# USB_Connectors.net
KiCad netlist of a schematic drawn in Altium Designer
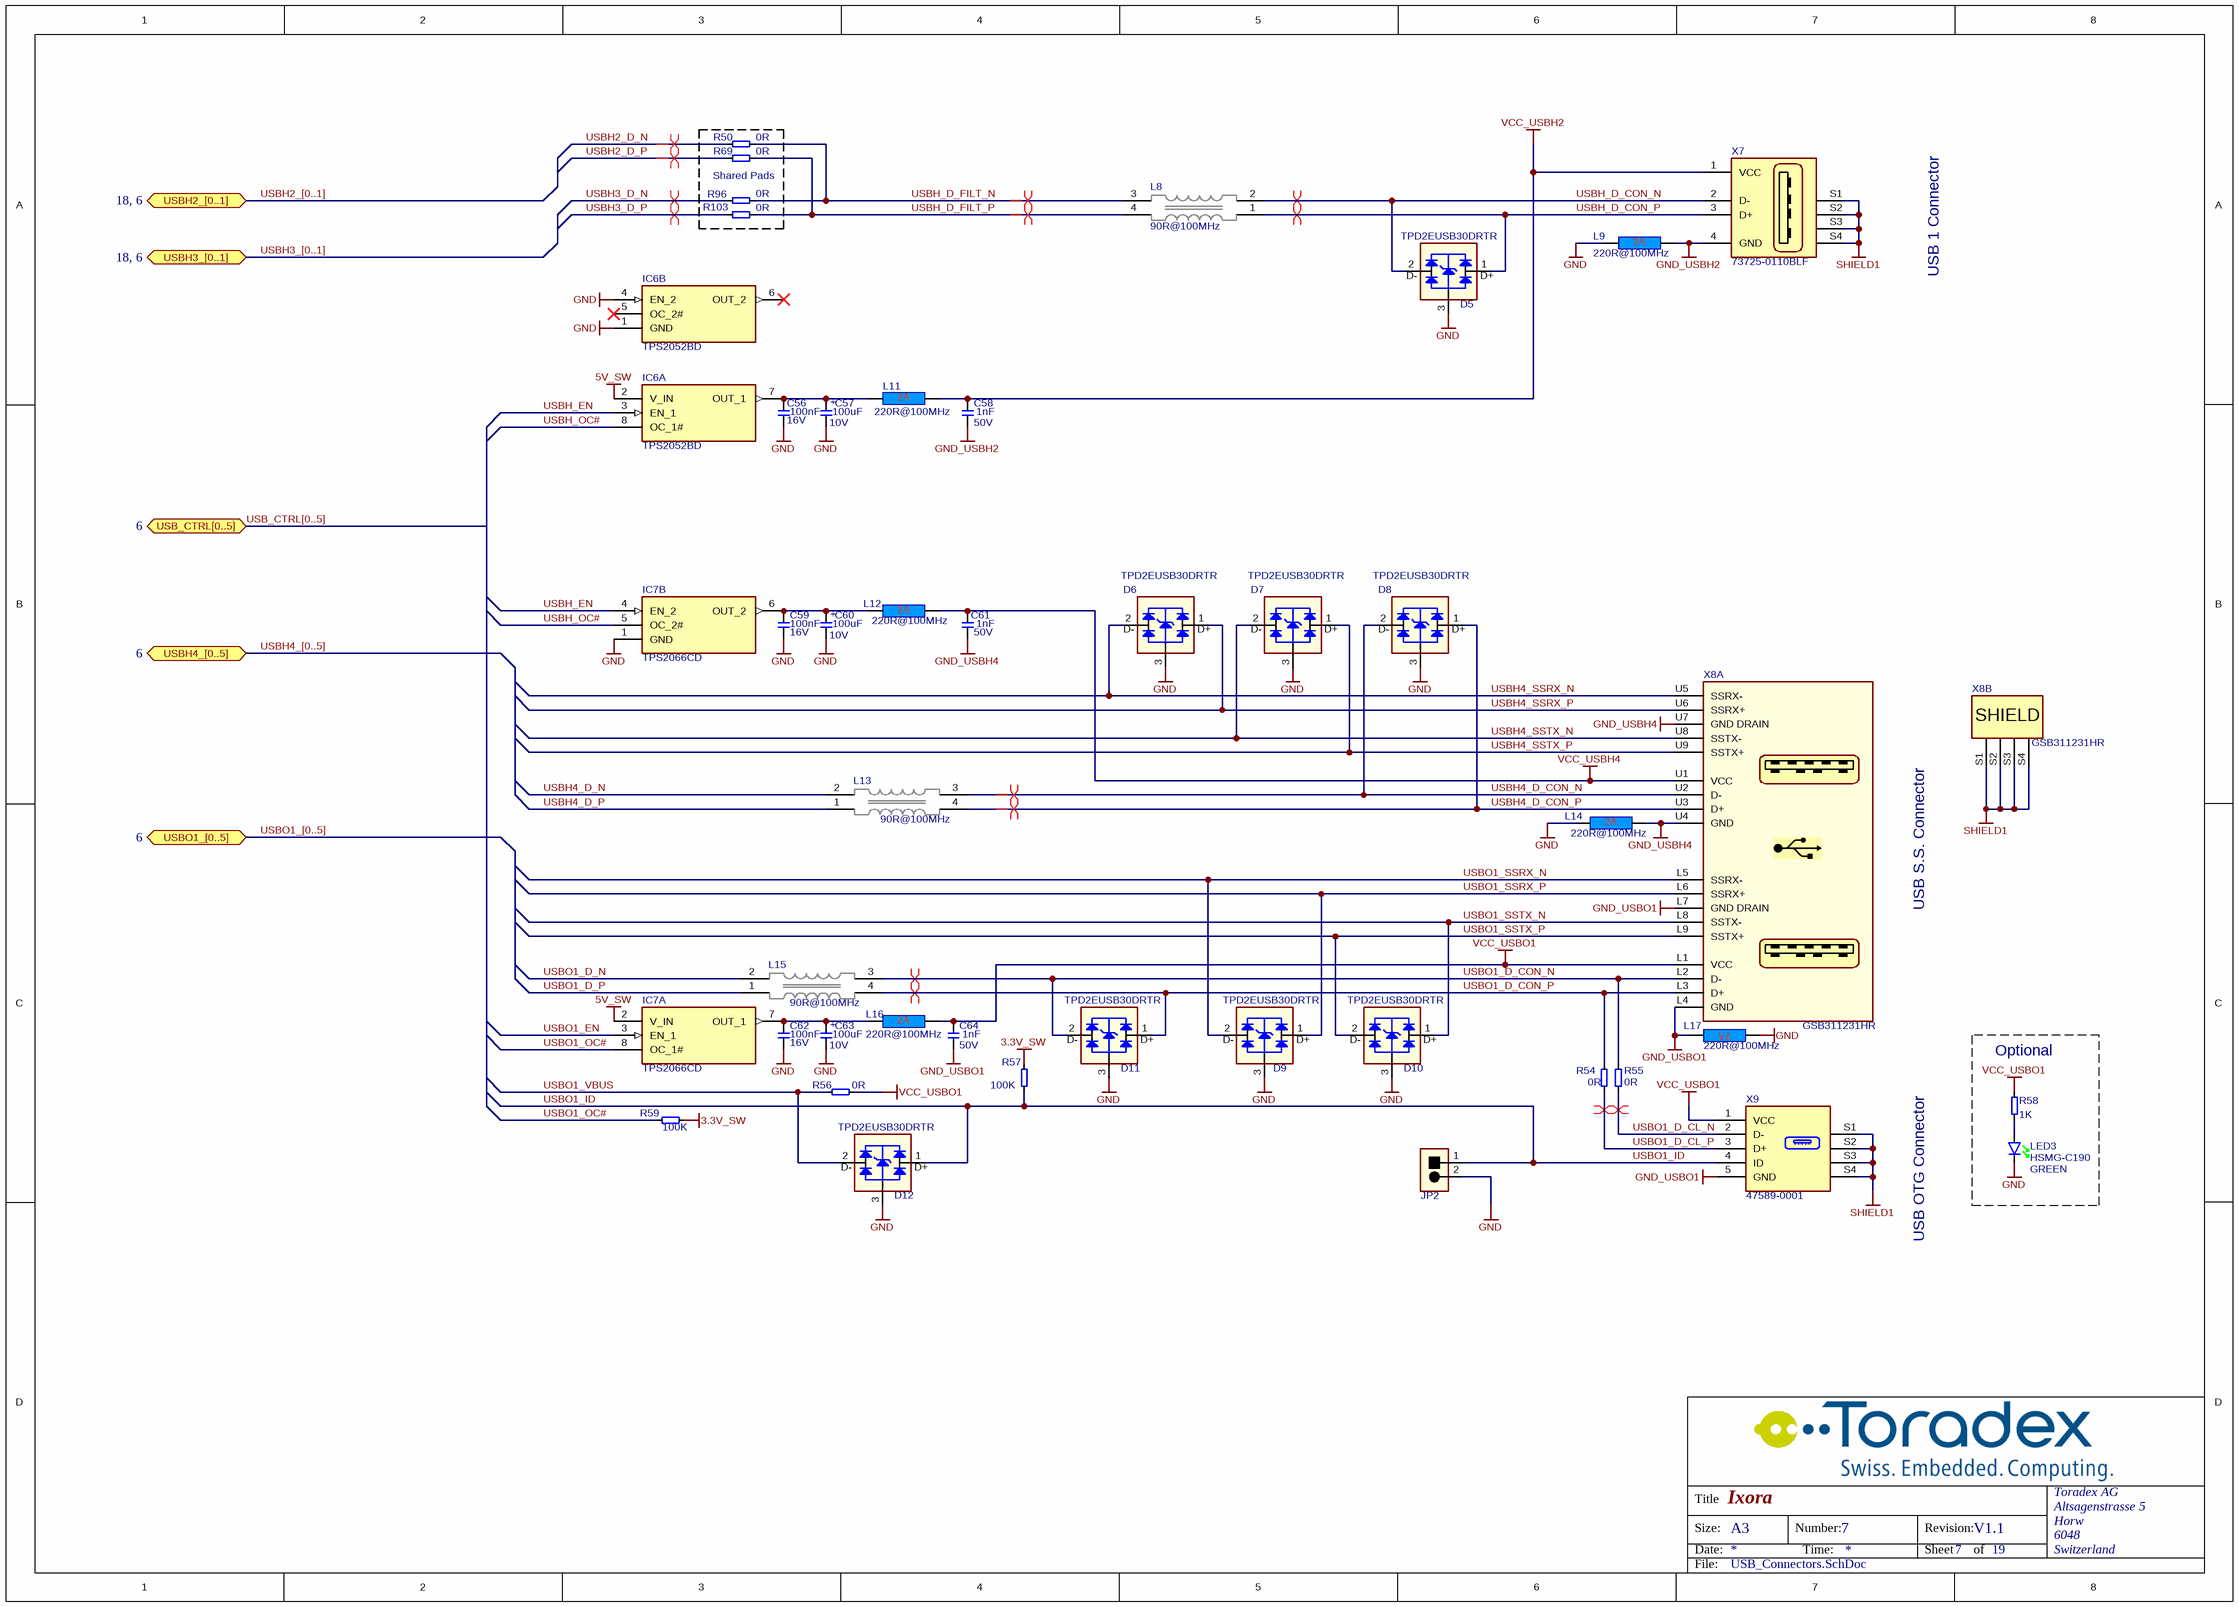
[diagram p0: USB_Connectors.SchDoc]

(export (version "E")
  (design (tool "Eeschema 10.0.6"))
  (components
    (comp (ref "C56")
      (value "100nF")
      (footprint "CAPC1005X60N")
      (description "Capacitor Ceramic X7R 100nF 16V 10% 0402")
      (fields (field (name "TOLERANCE") "10%") (field (name "RATING") "16V"))
      (libsource (lib "Ixora") (part "C-X7R-100nF-16V-10%-0402"))
    )
    (comp (ref "C57")
      (value "100uF")
      (footprint "CAPMP6032X280N")
      (description "Capacitor TA 100uF 10V 10% 6032")
      (fields (field (name "TOLERANCE") "10%") (field (name "RATING") "10V"))
      (libsource (lib "Ixora") (part "C-TA-100uF-10V-10%-6032"))
    )
    (comp (ref "C58")
      (value "1nF")
      (footprint "CAPC1005X60N")
      (description "Capacitor Ceramic X7R 1nF 50V 10% 0402")
      (fields (field (name "TOLERANCE") "10%") (field (name "RATING") "50V"))
      (libsource (lib "Ixora") (part "C-X7R-1nF-50V-10%-0402"))
    )
    (comp (ref "C59")
      (value "100nF")
      (footprint "CAPC1005X60N")
      (description "Capacitor Ceramic X7R 100nF 16V 10% 0402")
      (fields (field (name "TOLERANCE") "10%") (field (name "RATING") "16V"))
      (libsource (lib "Ixora") (part "C-X7R-100nF-16V-10%-0402"))
    )
    (comp (ref "C60")
      (value "100uF")
      (footprint "CAPMP6032X280N")
      (description "Capacitor TA 100uF 10V 10% 6032")
      (fields (field (name "TOLERANCE") "10%") (field (name "RATING") "10V"))
      (libsource (lib "Ixora") (part "C-TA-100uF-10V-10%-6032"))
    )
    (comp (ref "C61")
      (value "1nF")
      (footprint "CAPC1005X60N")
      (description "Capacitor Ceramic X7R 1nF 50V 10% 0402")
      (fields (field (name "TOLERANCE") "10%") (field (name "RATING") "50V"))
      (libsource (lib "Ixora") (part "C-X7R-1nF-50V-10%-0402"))
    )
    (comp (ref "C62")
      (value "100nF")
      (footprint "CAPC1005X60N")
      (description "Capacitor Ceramic X7R 100nF 16V 10% 0402")
      (fields (field (name "TOLERANCE") "10%") (field (name "RATING") "16V"))
      (libsource (lib "Ixora") (part "C-X7R-100nF-16V-10%-0402"))
    )
    (comp (ref "C63")
      (value "100uF")
      (footprint "CAPMP6032X280N")
      (description "Capacitor TA 100uF 10V 10% 6032")
      (fields (field (name "TOLERANCE") "10%") (field (name "RATING") "10V"))
      (libsource (lib "Ixora") (part "C-TA-100uF-10V-10%-6032"))
    )
    (comp (ref "C64")
      (value "1nF")
      (footprint "CAPC1005X60N")
      (description "Capacitor Ceramic X7R 1nF 50V 10% 0402")
      (fields (field (name "TOLERANCE") "10%") (field (name "RATING") "50V"))
      (libsource (lib "Ixora") (part "C-X7R-1nF-50V-10%-0402"))
    )
    (comp (ref "D5")
      (value "TPD2EUSB30DRTR")
      (footprint "T_TI_TPD2EUSB30DRTR")
      (description "2 Channel Protection for Super Speed USB3.0")
      (fields (field (name "MANUFACTURER PART NO.") "TPD2EUSB30DRTR"))
      (libsource (lib "Ixora") (part "D-TI-TPD2EUSB30DRTR"))
    )
    (comp (ref "D6")
      (value "TPD2EUSB30DRTR")
      (footprint "T_TI_TPD2EUSB30DRTR")
      (description "2 Channel Protection for Super Speed USB3.0")
      (fields (field (name "MANUFACTURER PART NO.") "TPD2EUSB30DRTR"))
      (libsource (lib "Ixora") (part "D-TI-TPD2EUSB30DRTR"))
    )
    (comp (ref "D7")
      (value "TPD2EUSB30DRTR")
      (footprint "T_TI_TPD2EUSB30DRTR")
      (description "2 Channel Protection for Super Speed USB3.0")
      (fields (field (name "MANUFACTURER PART NO.") "TPD2EUSB30DRTR"))
      (libsource (lib "Ixora") (part "D-TI-TPD2EUSB30DRTR"))
    )
    (comp (ref "D8")
      (value "TPD2EUSB30DRTR")
      (footprint "T_TI_TPD2EUSB30DRTR")
      (description "2 Channel Protection for Super Speed USB3.0")
      (fields (field (name "MANUFACTURER PART NO.") "TPD2EUSB30DRTR"))
      (libsource (lib "") (part "D-TI-TPD2EUSB30DRTR_2"))
    )
    (comp (ref "D9")
      (value "TPD2EUSB30DRTR")
      (footprint "T_TI_TPD2EUSB30DRTR")
      (description "2 Channel Protection for Super Speed USB3.0")
      (fields (field (name "MANUFACTURER PART NO.") "TPD2EUSB30DRTR"))
      (libsource (lib "Ixora") (part "D-TI-TPD2EUSB30DRTR"))
    )
    (comp (ref "D10")
      (value "TPD2EUSB30DRTR")
      (footprint "T_TI_TPD2EUSB30DRTR")
      (description "2 Channel Protection for Super Speed USB3.0")
      (fields (field (name "MANUFACTURER PART NO.") "TPD2EUSB30DRTR"))
      (libsource (lib "") (part "D-TI-TPD2EUSB30DRTR_1"))
    )
    (comp (ref "D11")
      (value "TPD2EUSB30DRTR")
      (footprint "T_TI_TPD2EUSB30DRTR")
      (description "2 Channel Protection for Super Speed USB3.0")
      (fields (field (name "MANUFACTURER PART NO.") "TPD2EUSB30DRTR"))
      (libsource (lib "Ixora") (part "D-TI-TPD2EUSB30DRTR"))
    )
    (comp (ref "D12")
      (value "TPD2EUSB30DRTR")
      (footprint "T_TI_TPD2EUSB30DRTR")
      (description "2 Channel Protection for Super Speed USB3.0")
      (fields (field (name "MANUFACTURER PART NO.") "TPD2EUSB30DRTR"))
      (libsource (lib "Ixora") (part "D-TI-TPD2EUSB30DRTR"))
    )
    (comp (ref "IC6")
      (value "TPS2052BD")
      (footprint "SOIC127P600X173-8N")
      (description "Dual High Side Switch With OC_DET 500mA/CH")
      (fields (field (name "MANUFACTURER PART NO.") "TPS2052BD"))
      (libsource (lib "Ixora") (part "IC-TI-TPS2052BD"))
    )
    (comp (ref "IC7")
      (value "TPS2066CD")
      (footprint "SOIC127P600X173-8N")
      (description "1A Dual High Side Switch (Current Limiting (Fixed), Over Temperature, Reverse Current, UVLO)")
      (fields (field (name "MANUFACTURER PART NO.") "TPS2066CD"))
      (libsource (lib "Ixora") (part "IC-TI-TPS2066CD"))
    )
    (comp (ref "JP2")
      (value "TSW-101-07-G-D")
      (footprint "T_Samtec_TSW-101-07-G-D")
      (description "Header male, 1x2 Pins, 2.54 mm pitch")
      (libsource (lib "Ixora") (part "CON-Samtec-TSW-101-07-G-D"))
    )
    (comp (ref "L8")
      (value "90R@100MHz")
      (footprint "T_Murata_DLW21SN900SQ2")
      (description "Common Mode Choke High Speed 90R 330mA")
      (fields (field (name "TOLERANCE") "25%") (field (name "MANUFACTURER PART NO.") "DLW21SN900SQ2"))
      (libsource (lib "") (part "L-Murata-DLW21SN900SQ2-90R@100MHz-330mA-25%_1"))
    )
    (comp (ref "L9")
      (value "220R@100MHz")
      (footprint "INDC1608X95N")
      (description "220R@100MHz 2A EMI FILTER")
      (fields (field (name "TOLERANCE") "25%"))
      (libsource (lib "Ixora") (part "L-220R@100MHz-2A-25%-0603"))
    )
    (comp (ref "L11")
      (value "220R@100MHz")
      (footprint "INDC1608X95N")
      (description "220R@100MHz 2A EMI FILTER")
      (fields (field (name "TOLERANCE") "25%"))
      (libsource (lib "Ixora") (part "L-220R@100MHz-2A-25%-0603"))
    )
    (comp (ref "L12")
      (value "220R@100MHz")
      (footprint "INDC1608X95N")
      (description "220R@100MHz 2A EMI FILTER")
      (fields (field (name "TOLERANCE") "25%"))
      (libsource (lib "Ixora") (part "L-220R@100MHz-2A-25%-0603"))
    )
    (comp (ref "L13")
      (value "90R@100MHz")
      (footprint "T_Murata_DLW21SN900SQ2")
      (description "Common Mode Choke High Speed 90R 330mA")
      (fields (field (name "TOLERANCE") "25%") (field (name "MANUFACTURER PART NO.") "DLW21SN900SQ2"))
      (libsource (lib "Ixora") (part "L-Murata-DLW21SN900SQ2-90R@100MHz-330mA-25%"))
    )
    (comp (ref "L14")
      (value "220R@100MHz")
      (footprint "INDC1608X95N")
      (description "220R@100MHz 2A EMI FILTER")
      (fields (field (name "TOLERANCE") "25%"))
      (libsource (lib "Ixora") (part "L-220R@100MHz-2A-25%-0603"))
    )
    (comp (ref "L15")
      (value "90R@100MHz")
      (footprint "T_Murata_DLW21SN900SQ2")
      (description "Common Mode Choke High Speed 90R 330mA")
      (fields (field (name "TOLERANCE") "25%") (field (name "MANUFACTURER PART NO.") "DLW21SN900SQ2"))
      (libsource (lib "Ixora") (part "L-Murata-DLW21SN900SQ2-90R@100MHz-330mA-25%"))
    )
    (comp (ref "L16")
      (value "220R@100MHz")
      (footprint "INDC1608X95N")
      (description "220R@100MHz 2A EMI FILTER")
      (fields (field (name "TOLERANCE") "25%"))
      (libsource (lib "Ixora") (part "L-220R@100MHz-2A-25%-0603"))
    )
    (comp (ref "L17")
      (value "220R@100MHz")
      (footprint "INDC1608X95N")
      (description "220R@100MHz 2A EMI FILTER")
      (fields (field (name "TOLERANCE") "25%"))
      (libsource (lib "") (part "L-220R@100MHz-2A-25%-0603_1"))
    )
    (comp (ref "LED3")
      (value "LED")
      (footprint "LEDC1608X80N_G")
      (description "Surface mount LED green 20mA")
      (fields (field (name "MANUFACTURER PART NO.") "HSMG-C190") (field (name "COLOR") "GREEN"))
      (libsource (lib "Ixora") (part "LED-Avago-HSMG-C190"))
    )
    (comp (ref "R50")
      (value "0R")
      (footprint "T_RESC0603X30N")
      (description "Resistor 0 ohm 63mW 1% 0603")
      (fields (field (name "TOLERANCE") "1%"))
      (libsource (lib "Ixora") (part "R-0R-63mW-1%-0603"))
    )
    (comp (ref "R54")
      (value "0R")
      (footprint "RESC1005X40N")
      (description "Resistor 0 ohm 63mW 1% 0402")
      (fields (field (name "TOLERANCE") "1%"))
      (libsource (lib "Ixora") (part "R-0R-63mW-1%-0402"))
    )
    (comp (ref "R55")
      (value "0R")
      (footprint "RESC1005X40N")
      (description "Resistor 0 ohm 63mW 1% 0402")
      (fields (field (name "TOLERANCE") "1%"))
      (libsource (lib "Ixora") (part "R-0R-63mW-1%-0402"))
    )
    (comp (ref "R56")
      (value "0R")
      (footprint "RESC1005X40N")
      (description "Resistor 0 ohm 63mW 1% 0402")
      (fields (field (name "TOLERANCE") "1%"))
      (libsource (lib "Ixora") (part "R-0R-63mW-1%-0402"))
    )
    (comp (ref "R57")
      (value "100K")
      (footprint "RESC1005X40N")
      (description "Resistor 100 Kohm 63mW 5% 0402")
      (fields (field (name "TOLERANCE") "5%"))
      (libsource (lib "Ixora") (part "R-100KR-63mW-5%-0402"))
    )
    (comp (ref "R58")
      (value "1K")
      (footprint "RESC1005X40N")
      (description "Resistor 1 Kohm 63mW 5% 0402")
      (fields (field (name "TOLERANCE") "5%"))
      (libsource (lib "Ixora") (part "R-1KR-63mW-5%-0402"))
    )
    (comp (ref "R59")
      (value "100K")
      (footprint "RESC1005X40N")
      (description "Resistor 100 Kohm 63mW 5% 0402")
      (fields (field (name "TOLERANCE") "5%"))
      (libsource (lib "Ixora") (part "R-100KR-63mW-5%-0402"))
    )
    (comp (ref "R69")
      (value "0R")
      (footprint "T_RESC0603X30N")
      (description "Resistor 0 ohm 63mW 1% 0603")
      (fields (field (name "TOLERANCE") "1%"))
      (libsource (lib "Ixora") (part "R-0R-63mW-1%-0603"))
    )
    (comp (ref "R96")
      (value "0R")
      (footprint "T_RESC0603X30N")
      (description "Resistor 0 ohm 63mW 1% 0603")
      (fields (field (name "TOLERANCE") "1%"))
      (libsource (lib "Ixora") (part "R-0R-63mW-1%-0603"))
    )
    (comp (ref "R103")
      (value "0R")
      (footprint "T_RESC0603X30N")
      (description "Resistor 0 ohm 63mW 1% 0603")
      (fields (field (name "TOLERANCE") "1%"))
      (libsource (lib "Ixora") (part "R-0R-63mW-1%-0603"))
    )
    (comp (ref "X7")
      (value "CON-Fci-73725-0110BLF")
      (footprint "T_FCI_73725-0110BLF")
      (description "USB Type A Connector")
      (fields (field (name "MANUFACTURER PART NO.") "73725-0110BLF"))
      (libsource (lib "Ixora") (part "CON-Fci-73725-0110BLF"))
    )
    (comp (ref "X8")
      (value "GSB311231HR")
      (footprint "T_AMPHENOL_ GSB311231HR")
      (description "USB 3.0 double row, Type A")
      (fields (field (name "MANUFACTURER PART NO.") "GSB311231HR"))
      (libsource (lib "Ixora") (part "CON-Amphenol-GSB311231HR"))
    )
    (comp (ref "X9")
      (value "CON-Molex-47589-0001-5-0.65")
      (footprint "T_Molex_47589-0001")
      (description "Micro USB OTG Connector")
      (fields (field (name "MANUFACTURER PART NO.") "47589-0001"))
      (libsource (lib "Ixora") (part "CON-Molex-47589-0001-5-0.65"))
    )
  )
  (nets
    (net (code "23") (name "/USBH2_D_N") (class "Default")
      (node (ref "R50") (pin "1") (pinfunction "1_1") (pintype "passive"))
    )
    (net (code "24") (name "/USBH2_D_P") (class "Default")
      (node (ref "R69") (pin "1") (pinfunction "1_1") (pintype "passive"))
    )
    (net (code "26") (name "/USBH3_D_N") (class "Default")
      (node (ref "R96") (pin "1") (pinfunction "1_1") (pintype "passive"))
    )
    (net (code "27") (name "/USBH3_D_P") (class "Default")
      (node (ref "R103") (pin "1") (pinfunction "1_1") (pintype "passive"))
    )
    (net (code "29") (name "/USBH4_D_CON_N") (class "Default")
      (node (ref "D8") (pin "2") (pinfunction "D-_2") (pintype "power_in"))
      (node (ref "L13") (pin "3") (pinfunction "3_3") (pintype "passive"))
      (node (ref "X8") (pin "U2") (pinfunction "D-_U2") (pintype "passive"))
    )
    (net (code "30") (name "/USBH4_D_CON_P") (class "Default")
      (node (ref "D8") (pin "1") (pinfunction "D+_1") (pintype "power_in"))
      (node (ref "L13") (pin "4") (pinfunction "4_4") (pintype "passive"))
      (node (ref "X8") (pin "U3") (pinfunction "D+_U3") (pintype "passive"))
    )
    (net (code "31") (name "/USBH4_D_N") (class "Default")
      (node (ref "L13") (pin "2") (pinfunction "2_2") (pintype "passive"))
    )
    (net (code "32") (name "/USBH4_D_P") (class "Default")
      (node (ref "L13") (pin "1") (pinfunction "1_1") (pintype "passive"))
    )
    (net (code "33") (name "/USBH4_SSRX_N") (class "Default")
      (node (ref "D6") (pin "2") (pinfunction "D-_2") (pintype "power_in"))
      (node (ref "X8") (pin "U5") (pinfunction "SSRX-_U5") (pintype "power_in"))
    )
    (net (code "34") (name "/USBH4_SSRX_P") (class "Default")
      (node (ref "D6") (pin "1") (pinfunction "D+_1") (pintype "power_in"))
      (node (ref "X8") (pin "U6") (pinfunction "SSRX+_U6") (pintype "power_in"))
    )
    (net (code "35") (name "/USBH4_SSTX_N") (class "Default")
      (node (ref "D7") (pin "2") (pinfunction "D-_2") (pintype "power_in"))
      (node (ref "X8") (pin "U8") (pinfunction "SSTX-_U8") (pintype "power_in"))
    )
    (net (code "36") (name "/USBH4_SSTX_P") (class "Default")
      (node (ref "D7") (pin "1") (pinfunction "D+_1") (pintype "power_in"))
      (node (ref "X8") (pin "U9") (pinfunction "SSTX+_U9") (pintype "power_in"))
    )
    (net (code "38") (name "/USBH_D_CON_N") (class "Default")
      (node (ref "D5") (pin "2") (pinfunction "D-_2") (pintype "power_in"))
      (node (ref "L8") (pin "2") (pinfunction "2_2") (pintype "passive"))
      (node (ref "X7") (pin "2") (pinfunction "D-_2") (pintype "passive"))
    )
    (net (code "39") (name "/USBH_D_CON_P") (class "Default")
      (node (ref "D5") (pin "1") (pinfunction "D+_1") (pintype "power_in"))
      (node (ref "L8") (pin "1") (pinfunction "1_1") (pintype "passive"))
      (node (ref "X7") (pin "3") (pinfunction "D+_3") (pintype "passive"))
    )
    (net (code "40") (name "/USBH_D_FILT_N") (class "Default")
      (node (ref "L8") (pin "3") (pinfunction "3_3") (pintype "passive"))
      (node (ref "R50") (pin "2") (pinfunction "2_2") (pintype "passive"))
      (node (ref "R96") (pin "2") (pinfunction "2_2") (pintype "passive"))
    )
    (net (code "41") (name "/USBH_D_FILT_P") (class "Default")
      (node (ref "L8") (pin "4") (pinfunction "4_4") (pintype "passive"))
      (node (ref "R103") (pin "2") (pinfunction "2_2") (pintype "passive"))
      (node (ref "R69") (pin "2") (pinfunction "2_2") (pintype "passive"))
    )
    (net (code "42") (name "/USBH_EN") (class "Default")
      (node (ref "IC6") (pin "3") (pinfunction "EN_1_3") (pintype "input"))
      (node (ref "IC7") (pin "4") (pinfunction "EN_2_4") (pintype "input"))
    )
    (net (code "43") (name "/USBH_OC#") (class "Default")
      (node (ref "IC6") (pin "8") (pinfunction "OC_1#_8") (pintype "passive"))
      (node (ref "IC7") (pin "5") (pinfunction "OC_2#_5") (pintype "passive"))
    )
    (net (code "44") (name "/USBO1_D_CL_N") (class "Default")
      (node (ref "R55") (pin "1") (pinfunction "1_1") (pintype "passive"))
      (node (ref "X9") (pin "2") (pinfunction "D-_2") (pintype "passive"))
    )
    (net (code "45") (name "/USBO1_D_CL_P") (class "Default")
      (node (ref "R54") (pin "1") (pinfunction "1_1") (pintype "passive"))
      (node (ref "X9") (pin "3") (pinfunction "D+_3") (pintype "passive"))
    )
    (net (code "46") (name "/USBO1_D_CON_N") (class "Default")
      (node (ref "D11") (pin "2") (pinfunction "D-_2") (pintype "power_in"))
      (node (ref "L15") (pin "3") (pinfunction "3_3") (pintype "passive"))
      (node (ref "R55") (pin "2") (pinfunction "2_2") (pintype "passive"))
      (node (ref "X8") (pin "L2") (pinfunction "D-_L2") (pintype "passive"))
    )
    (net (code "47") (name "/USBO1_D_CON_P") (class "Default")
      (node (ref "D11") (pin "1") (pinfunction "D+_1") (pintype "power_in"))
      (node (ref "L15") (pin "4") (pinfunction "4_4") (pintype "passive"))
      (node (ref "R54") (pin "2") (pinfunction "2_2") (pintype "passive"))
      (node (ref "X8") (pin "L3") (pinfunction "D+_L3") (pintype "passive"))
    )
    (net (code "48") (name "/USBO1_D_N") (class "Default")
      (node (ref "L15") (pin "2") (pinfunction "2_2") (pintype "passive"))
    )
    (net (code "49") (name "/USBO1_D_P") (class "Default")
      (node (ref "L15") (pin "1") (pinfunction "1_1") (pintype "passive"))
    )
    (net (code "50") (name "/USBO1_EN") (class "Default")
      (node (ref "IC7") (pin "3") (pinfunction "EN_1_3") (pintype "input"))
    )
    (net (code "51") (name "/USBO1_ID") (class "Default")
      (node (ref "D12") (pin "1") (pinfunction "D+_1") (pintype "power_in"))
      (node (ref "JP2") (pin "1") (pinfunction "1_1") (pintype "passive"))
      (node (ref "R57") (pin "2") (pinfunction "2_2") (pintype "passive"))
      (node (ref "X9") (pin "4") (pinfunction "ID_4") (pintype "passive"))
    )
    (net (code "52") (name "/USBO1_OC#") (class "Default")
      (node (ref "IC7") (pin "8") (pinfunction "OC_1#_8") (pintype "passive"))
      (node (ref "R59") (pin "1") (pinfunction "1_1") (pintype "passive"))
    )
    (net (code "53") (name "/USBO1_SSRX_N") (class "Default")
      (node (ref "D9") (pin "2") (pinfunction "D-_2") (pintype "power_in"))
      (node (ref "X8") (pin "L5") (pinfunction "SSRX-_L5") (pintype "power_in"))
    )
    (net (code "54") (name "/USBO1_SSRX_P") (class "Default")
      (node (ref "D9") (pin "1") (pinfunction "D+_1") (pintype "power_in"))
      (node (ref "X8") (pin "L6") (pinfunction "SSRX+_L6") (pintype "power_in"))
    )
    (net (code "55") (name "/USBO1_SSTX_N") (class "Default")
      (node (ref "D10") (pin "1") (pinfunction "D+_1") (pintype "power_in"))
      (node (ref "X8") (pin "L8") (pinfunction "SSTX-_L8") (pintype "power_in"))
    )
    (net (code "56") (name "/USBO1_SSTX_P") (class "Default")
      (node (ref "D10") (pin "2") (pinfunction "D-_2") (pintype "power_in"))
      (node (ref "X8") (pin "L9") (pinfunction "SSTX+_L9") (pintype "power_in"))
    )
    (net (code "57") (name "/USBO1_VBUS") (class "Default")
      (node (ref "D12") (pin "2") (pinfunction "D-_2") (pintype "power_in"))
      (node (ref "R56") (pin "1") (pinfunction "1_1") (pintype "passive"))
    )
    (net (code "60") (name "3.3V_SW") (class "Default")
      (node (ref "R57") (pin "1") (pinfunction "1_1") (pintype "passive"))
      (node (ref "R59") (pin "2") (pinfunction "2_2") (pintype "passive"))
    )
    (net (code "61") (name "5V_SW") (class "Default")
      (node (ref "IC6") (pin "2") (pinfunction "V_IN_2") (pintype "power_in"))
      (node (ref "IC7") (pin "2") (pinfunction "V_IN_2") (pintype "power_in"))
    )
    (net (code "62") (name "GND") (class "Default")
      (node (ref "C56") (pin "1") (pinfunction "1_1") (pintype "passive"))
      (node (ref "C57") (pin "2") (pinfunction "2_2") (pintype "passive"))
      (node (ref "C59") (pin "1") (pinfunction "1_1") (pintype "passive"))
      (node (ref "C60") (pin "2") (pinfunction "2_2") (pintype "passive"))
      (node (ref "C62") (pin "1") (pinfunction "1_1") (pintype "passive"))
      (node (ref "C63") (pin "2") (pinfunction "2_2") (pintype "passive"))
      (node (ref "D10") (pin "3") (pinfunction "3_3") (pintype "power_in"))
      (node (ref "D11") (pin "3") (pinfunction "3_3") (pintype "power_in"))
      (node (ref "D12") (pin "3") (pinfunction "3_3") (pintype "power_in"))
      (node (ref "D5") (pin "3") (pinfunction "3_3") (pintype "power_in"))
      (node (ref "D6") (pin "3") (pinfunction "3_3") (pintype "power_in"))
      (node (ref "D7") (pin "3") (pinfunction "3_3") (pintype "power_in"))
      (node (ref "D8") (pin "3") (pinfunction "3_3") (pintype "power_in"))
      (node (ref "D9") (pin "3") (pinfunction "3_3") (pintype "power_in"))
      (node (ref "IC6") (pin "1") (pinfunction "GND_1") (pintype "power_in"))
      (node (ref "IC6") (pin "4") (pinfunction "EN_2_4") (pintype "input"))
      (node (ref "IC7") (pin "1") (pinfunction "GND_1") (pintype "power_in"))
      (node (ref "JP2") (pin "2") (pinfunction "2_2") (pintype "passive"))
      (node (ref "L14") (pin "1") (pinfunction "1_1") (pintype "passive"))
      (node (ref "L17") (pin "1") (pinfunction "1_1") (pintype "passive"))
      (node (ref "L9") (pin "1") (pinfunction "1_1") (pintype "passive"))
      (node (ref "LED3") (pin "1") (pinfunction "K_1") (pintype "passive"))
    )
    (net (code "63") (name "GND_USBH2") (class "Default")
      (node (ref "C58") (pin "1") (pinfunction "1_1") (pintype "passive"))
      (node (ref "L9") (pin "2") (pinfunction "2_2") (pintype "passive"))
      (node (ref "X7") (pin "4") (pinfunction "GND_4") (pintype "power_in"))
    )
    (net (code "64") (name "GND_USBH4") (class "Default")
      (node (ref "C61") (pin "1") (pinfunction "1_1") (pintype "passive"))
      (node (ref "L14") (pin "2") (pinfunction "2_2") (pintype "passive"))
      (node (ref "X8") (pin "U4") (pinfunction "GND_U4") (pintype "power_in"))
      (node (ref "X8") (pin "U7") (pinfunction "GND_DRAIN_U7") (pintype "power_in"))
    )
    (net (code "65") (name "GND_USBO1") (class "Default")
      (node (ref "C64") (pin "1") (pinfunction "1_1") (pintype "passive"))
      (node (ref "L17") (pin "2") (pinfunction "2_2") (pintype "passive"))
      (node (ref "X8") (pin "L4") (pinfunction "GND_L4") (pintype "power_in"))
      (node (ref "X8") (pin "L7") (pinfunction "GND_DRAIN_L7") (pintype "power_in"))
      (node (ref "X9") (pin "5") (pinfunction "GND_5") (pintype "power_in"))
    )
    (net (code "66") (name "Net-(IC6A-OUT_1)") (class "Default")
      (node (ref "C56") (pin "2") (pinfunction "2_2") (pintype "passive"))
      (node (ref "C57") (pin "1") (pinfunction "1_1") (pintype "passive"))
      (node (ref "IC6") (pin "7") (pinfunction "OUT_1_7") (pintype "output"))
      (node (ref "L11") (pin "1") (pinfunction "1_1") (pintype "passive"))
    )
    (net (code "67") (name "Net-(IC7A-OUT_1)") (class "Default")
      (node (ref "C62") (pin "2") (pinfunction "2_2") (pintype "passive"))
      (node (ref "C63") (pin "1") (pinfunction "1_1") (pintype "passive"))
      (node (ref "IC7") (pin "7") (pinfunction "OUT_1_7") (pintype "output"))
      (node (ref "L16") (pin "1") (pinfunction "1_1") (pintype "passive"))
    )
    (net (code "68") (name "Net-(IC7B-OUT_2)") (class "Default")
      (node (ref "C59") (pin "2") (pinfunction "2_2") (pintype "passive"))
      (node (ref "C60") (pin "1") (pinfunction "1_1") (pintype "passive"))
      (node (ref "IC7") (pin "6") (pinfunction "OUT_2_6") (pintype "output"))
      (node (ref "L12") (pin "1") (pinfunction "1_1") (pintype "passive"))
    )
    (net (code "69") (name "Net-(LED3-A)") (class "Default")
      (node (ref "LED3") (pin "2") (pinfunction "A_2") (pintype "passive"))
      (node (ref "R58") (pin "2") (pinfunction "2_2") (pintype "passive"))
    )
    (net (code "70") (name "SHIELD1") (class "Default")
      (node (ref "X7") (pin "S1") (pinfunction "S1_S1") (pintype "passive"))
      (node (ref "X7") (pin "S2") (pinfunction "S2_S2") (pintype "passive"))
      (node (ref "X7") (pin "S3") (pinfunction "S3_S3") (pintype "passive"))
      (node (ref "X7") (pin "S4") (pinfunction "S4_S4") (pintype "passive"))
      (node (ref "X8") (pin "S1") (pinfunction "SHIELD_S1") (pintype "passive"))
      (node (ref "X8") (pin "S2") (pinfunction "SHIELD_S2") (pintype "passive"))
      (node (ref "X8") (pin "S3") (pinfunction "SHIELD_S3") (pintype "passive"))
      (node (ref "X8") (pin "S4") (pinfunction "SHIELD_S4") (pintype "passive"))
      (node (ref "X9") (pin "S1") (pinfunction "S1_S1") (pintype "passive"))
      (node (ref "X9") (pin "S2") (pinfunction "S2_S2") (pintype "passive"))
      (node (ref "X9") (pin "S3") (pinfunction "S3_S3") (pintype "passive"))
      (node (ref "X9") (pin "S4") (pinfunction "S4_S4") (pintype "passive"))
    )
    (net (code "71") (name "VCC_USBH2") (class "Default")
      (node (ref "C58") (pin "2") (pinfunction "2_2") (pintype "passive"))
      (node (ref "L11") (pin "2") (pinfunction "2_2") (pintype "passive"))
      (node (ref "X7") (pin "1") (pinfunction "VCC_1") (pintype "power_in"))
    )
    (net (code "72") (name "VCC_USBH4") (class "Default")
      (node (ref "C61") (pin "2") (pinfunction "2_2") (pintype "passive"))
      (node (ref "L12") (pin "2") (pinfunction "2_2") (pintype "passive"))
      (node (ref "X8") (pin "U1") (pinfunction "VCC_U1") (pintype "power_in"))
    )
    (net (code "73") (name "VCC_USBO1") (class "Default")
      (node (ref "C64") (pin "2") (pinfunction "2_2") (pintype "passive"))
      (node (ref "L16") (pin "2") (pinfunction "2_2") (pintype "passive"))
      (node (ref "R56") (pin "2") (pinfunction "2_2") (pintype "passive"))
      (node (ref "R58") (pin "1") (pinfunction "1_1") (pintype "passive"))
      (node (ref "X8") (pin "L1") (pinfunction "VCC_L1") (pintype "power_in"))
      (node (ref "X9") (pin "1") (pinfunction "VCC_1") (pintype "power_in"))
    )
    (net (code "74") (name "unconnected-(IC6B-OC_2#-Pad5)") (class "Default")
      (node (ref "IC6") (pin "5") (pinfunction "OC_2#_5") (pintype "passive+no_connect"))
    )
    (net (code "75") (name "unconnected-(IC6B-OUT_2-Pad6)") (class "Default")
      (node (ref "IC6") (pin "6") (pinfunction "OUT_2_6") (pintype "output+no_connect"))
    )
  )
)
